# max30100.net
KiCad netlist of a schematic drawn in EAGLE
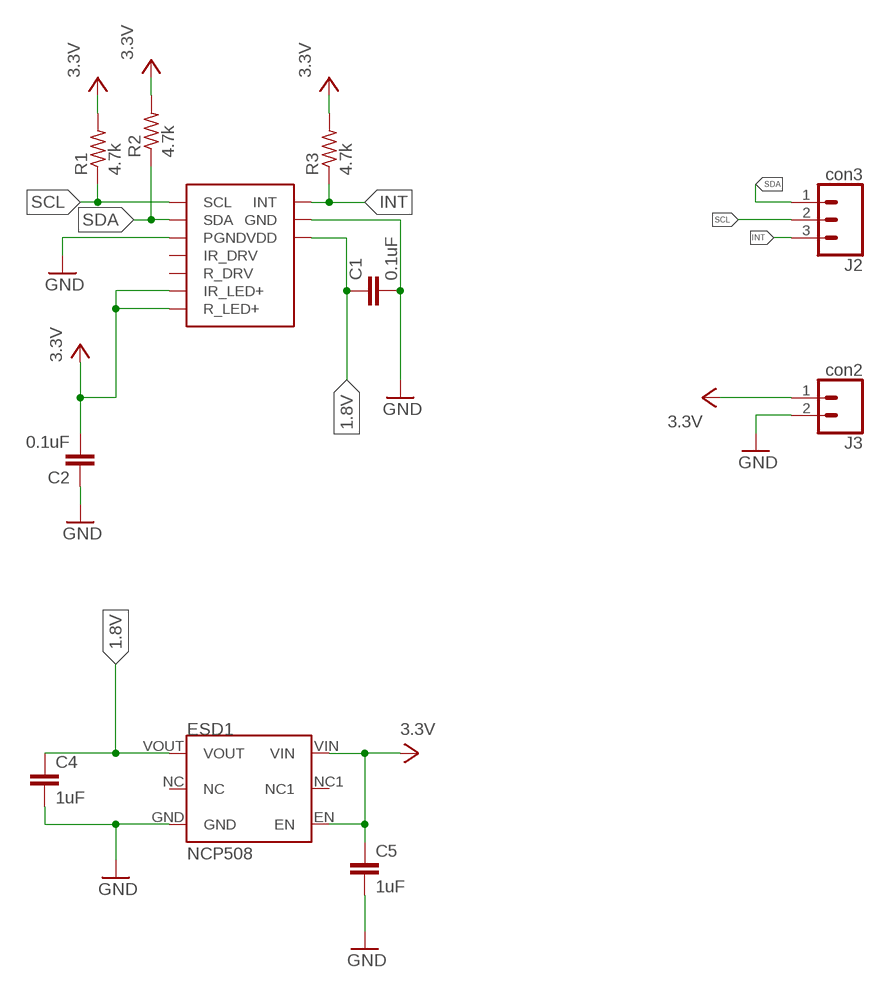
[diagram p0: schematic, sheet 1]

(export (version "E")
  (design (tool "Eeschema 10.0.6"))
  (components
    (comp (ref "C1")
      (value "0.1uF")
      (footprint "eagle-import:C0603")
      (libsource (lib "eagle-import") (part "rcl_334_C-EUC0603"))
    )
    (comp (ref "C2")
      (value "0.1uF")
      (footprint "eagle-import:C0603")
      (libsource (lib "eagle-import") (part "rcl_334_C-EUC0603"))
    )
    (comp (ref "C4")
      (value "1uF")
      (footprint "eagle-import:C0603K")
      (libsource (lib "eagle-import") (part "C-EUC0603K"))
    )
    (comp (ref "C5")
      (value "1uF")
      (footprint "eagle-import:C0603K")
      (libsource (lib "eagle-import") (part "C-EUC0603K"))
    )
    (comp (ref "ESD1")
      (value "NCP508")
      (footprint "eagle-import:UQFN6")
      (fields (field (name "MF") "STMicroelectronics") (field (name "MP") "USBULC6-2M6"))
      (libsource (lib "eagle-import") (part "NCP508"))
    )
    (comp (ref "J2")
      (value "con3")
      (footprint "eagle-import:1X03")
      (libsource (lib "eagle-import") (part "CONN_03"))
    )
    (comp (ref "J3")
      (value "con2")
      (footprint "eagle-import:1X02")
      (libsource (lib "eagle-import") (part "CONN_02"))
    )
    (comp (ref "R1")
      (value "4.7k")
      (footprint "eagle-import:R0603")
      (libsource (lib "eagle-import") (part "R-US_R0603"))
    )
    (comp (ref "R2")
      (value "4.7k")
      (footprint "eagle-import:R0603")
      (libsource (lib "eagle-import") (part "R-US_R0603"))
    )
    (comp (ref "R3")
      (value "4.7k")
      (footprint "eagle-import:R0603")
      (libsource (lib "eagle-import") (part "R-US_R0603"))
    )
    (comp (ref "U$1")
      (value "MAX30100")
      (footprint "eagle-import:MAX30100")
      (libsource (lib "eagle-import") (part "MAX30100"))
    )
  )
  (nets
    (net (code "1") (name "1.8V") (class "Default")
      (node (ref "C1") (pin "1") (pinfunction "1_1") (pintype "passive"))
      (node (ref "C4") (pin "1") (pinfunction "1_1") (pintype "passive"))
      (node (ref "ESD1") (pin "VOUT") (pinfunction "VOUT_VOUT") (pintype "bidirectional"))
      (node (ref "U$1") (pin "11") (pinfunction "VDD_11") (pintype "bidirectional"))
    )
    (net (code "2") (name "3.3V") (class "Default")
      (node (ref "C2") (pin "2") (pinfunction "2_2") (pintype "passive"))
      (node (ref "C5") (pin "1") (pinfunction "1_1") (pintype "passive"))
      (node (ref "ESD1") (pin "EN") (pinfunction "EN_EN") (pintype "bidirectional"))
      (node (ref "ESD1") (pin "VIN") (pinfunction "VIN_VIN") (pintype "bidirectional"))
      (node (ref "J3") (pin "1") (pinfunction "1_1") (pintype "passive"))
      (node (ref "R1") (pin "2") (pinfunction "2_2") (pintype "passive"))
      (node (ref "R2") (pin "2") (pinfunction "2_2") (pintype "passive"))
      (node (ref "R3") (pin "2") (pinfunction "2_2") (pintype "passive"))
      (node (ref "U$1") (pin "10") (pinfunction "IR_LED+_10") (pintype "bidirectional"))
      (node (ref "U$1") (pin "9") (pinfunction "R_LED+_9") (pintype "bidirectional"))
    )
    (net (code "3") (name "GND") (class "Default")
      (node (ref "C1") (pin "2") (pinfunction "2_2") (pintype "passive"))
      (node (ref "C2") (pin "1") (pinfunction "1_1") (pintype "passive"))
      (node (ref "C4") (pin "2") (pinfunction "2_2") (pintype "passive"))
      (node (ref "C5") (pin "2") (pinfunction "2_2") (pintype "passive"))
      (node (ref "ESD1") (pin "GND") (pinfunction "GND_GND") (pintype "bidirectional"))
      (node (ref "J3") (pin "2") (pinfunction "2_2") (pintype "passive"))
      (node (ref "U$1") (pin "12") (pinfunction "GND_12") (pintype "bidirectional"))
      (node (ref "U$1") (pin "4") (pinfunction "PGND_4") (pintype "bidirectional"))
    )
    (net (code "4") (name "INT") (class "Default")
      (node (ref "J2") (pin "3") (pinfunction "3_3") (pintype "passive"))
      (node (ref "R3") (pin "1") (pinfunction "1_1") (pintype "passive"))
      (node (ref "U$1") (pin "13") (pinfunction "INT_13") (pintype "bidirectional"))
    )
    (net (code "5") (name "SCL") (class "Default")
      (node (ref "J2") (pin "2") (pinfunction "2_2") (pintype "passive"))
      (node (ref "R1") (pin "1") (pinfunction "1_1") (pintype "passive"))
      (node (ref "U$1") (pin "2") (pinfunction "SCL_2") (pintype "bidirectional"))
    )
    (net (code "6") (name "SDA") (class "Default")
      (node (ref "J2") (pin "1") (pinfunction "1_1") (pintype "passive"))
      (node (ref "R2") (pin "1") (pinfunction "1_1") (pintype "passive"))
      (node (ref "U$1") (pin "3") (pinfunction "SDA_3") (pintype "bidirectional"))
    )
    (net (code "7") (name "unconnected-(ESD1-PadNC)") (class "Default")
      (node (ref "ESD1") (pin "NC") (pinfunction "NC_NC") (pintype "bidirectional"))
    )
    (net (code "8") (name "unconnected-(ESD1-PadNC1)") (class "Default")
      (node (ref "ESD1") (pin "NC1") (pinfunction "NC1_NC1") (pintype "bidirectional"))
    )
    (net (code "9") (name "unconnected-(U$1-IR_DRV-Pad5)") (class "Default")
      (node (ref "U$1") (pin "5") (pinfunction "IR_DRV_5") (pintype "bidirectional"))
    )
    (net (code "10") (name "unconnected-(U$1-R_DRV-Pad6)") (class "Default")
      (node (ref "U$1") (pin "6") (pinfunction "R_DRV_6") (pintype "bidirectional"))
    )
  )
)
